# Gyro_Mode.net
KiCad netlist of a schematic drawn in Altium Designer
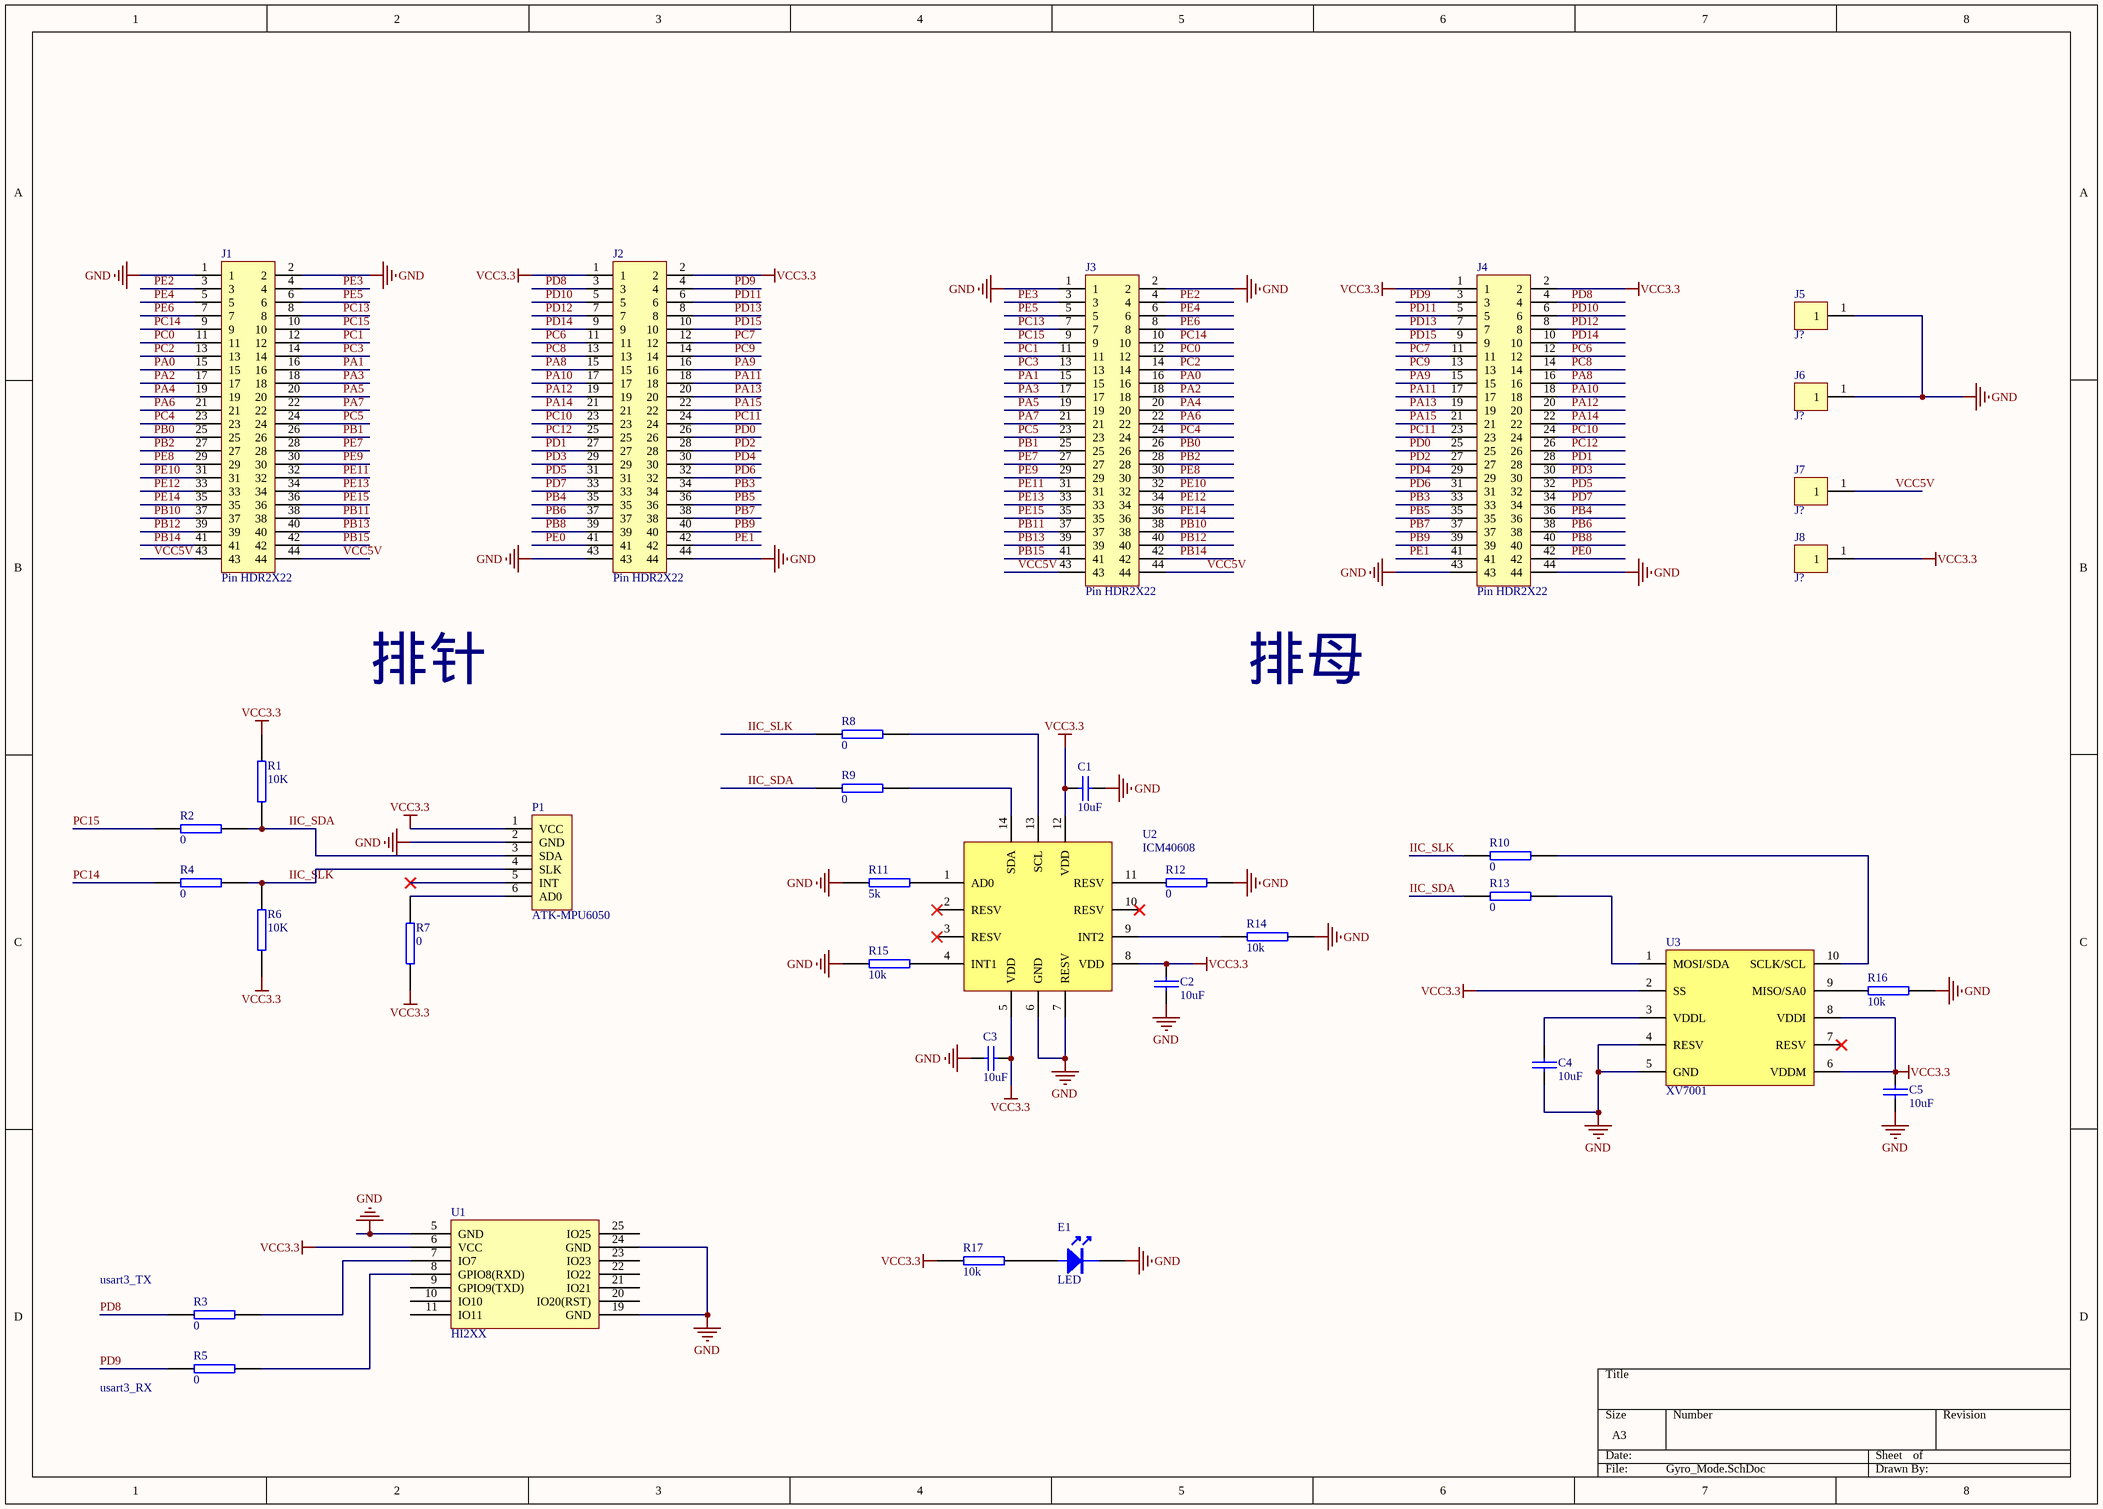
[diagram p0: Gyro_Mode.SchDoc]

(export (version "E")
  (design (tool "Eeschema 10.0.6"))
  (components
    (comp (ref "C1")
      (value "10uF")
      (footprint "0603")
      (description "无极电容")
      (libsource (lib "chenjd") (part "CAP Nonpolarity"))
    )
    (comp (ref "C2")
      (value "10uF")
      (footprint "0603")
      (description "无极电容")
      (libsource (lib "chenjd") (part "CAP Nonpolarity"))
    )
    (comp (ref "C3")
      (value "10uF")
      (footprint "0603")
      (description "无极电容")
      (libsource (lib "chenjd") (part "CAP Nonpolarity"))
    )
    (comp (ref "C4")
      (value "10uF")
      (footprint "0603")
      (description "无极电容")
      (libsource (lib "chenjd") (part "CAP Nonpolarity"))
    )
    (comp (ref "C5")
      (value "10uF")
      (footprint "0603")
      (description "无极电容")
      (libsource (lib "chenjd") (part "CAP Nonpolarity"))
    )
    (comp (ref "E1")
      (value "LED")
      (footprint "LED_0603L")
      (description "LED灯")
      (libsource (lib "chenjd") (part "LED"))
    )
    (comp (ref "J1")
      (value "Pin HDR2X22")
      (footprint "PIN HDR2X22/2.54SMD")
      (description "22pin双排2.54接口")
      (libsource (lib "chenjd") (part "Pin HDR2X22"))
    )
    (comp (ref "J2")
      (value "Pin HDR2X22")
      (footprint "PIN HDR2X22/2.54SMD")
      (description "22pin双排2.54接口")
      (libsource (lib "chenjd") (part "Pin HDR2X22"))
    )
    (comp (ref "J3")
      (value "Pin HDR2X22")
      (footprint "PIN HDR2X22/2.54SMD")
      (description "22pin双排2.54接口")
      (libsource (lib "chenjd") (part "Pin HDR2X22"))
    )
    (comp (ref "J4")
      (value "Pin HDR2X22")
      (footprint "PIN HDR2X22/2.54SMD")
      (description "22pin双排2.54接口")
      (libsource (lib "chenjd") (part "Pin HDR2X22"))
    )
    (comp (ref "J5")
      (value "J?")
      (footprint "固定柱")
      (description "固定柱")
      (libsource (lib "chenjd") (part "固定柱"))
    )
    (comp (ref "J6")
      (value "J?")
      (footprint "固定柱")
      (description "固定柱")
      (libsource (lib "chenjd") (part "固定柱"))
    )
    (comp (ref "J7")
      (value "J?")
      (footprint "固定柱")
      (description "固定柱")
      (libsource (lib "chenjd") (part "固定柱"))
    )
    (comp (ref "J8")
      (value "J?")
      (footprint "固定柱")
      (description "固定柱")
      (libsource (lib "chenjd") (part "固定柱"))
    )
    (comp (ref "P1")
      (value "ATK-MPU6050")
      (footprint "ATK-MPU6080")
      (fields (field (name "PUBLISHER") "Altium Limited"))
      (libsource (lib "chenjd") (part "ATK-MPU6050"))
    )
    (comp (ref "R1")
      (value "10K")
      (footprint "0603")
      (description "电阻")
      (libsource (lib "chenjd") (part "R"))
    )
    (comp (ref "R2") (value "0") (footprint "0603") (description "电阻") (libsource (lib "chenjd") (part "R")))
    (comp (ref "R3") (value "0") (footprint "0603") (description "电阻") (libsource (lib "chenjd") (part "R")))
    (comp (ref "R4") (value "0") (footprint "0603") (description "电阻") (libsource (lib "chenjd") (part "R")))
    (comp (ref "R5") (value "0") (footprint "0603") (description "电阻") (libsource (lib "chenjd") (part "R")))
    (comp (ref "R6")
      (value "10K")
      (footprint "0603")
      (description "电阻")
      (libsource (lib "chenjd") (part "R"))
    )
    (comp (ref "R7") (value "0") (footprint "0603") (description "电阻") (libsource (lib "chenjd") (part "R")))
    (comp (ref "R8") (value "0") (footprint "0603") (description "电阻") (libsource (lib "chenjd") (part "R")))
    (comp (ref "R9") (value "0") (footprint "0603") (description "电阻") (libsource (lib "chenjd") (part "R")))
    (comp (ref "R10") (value "0") (footprint "0603") (description "电阻") (libsource (lib "chenjd") (part "R")))
    (comp (ref "R11")
      (value "5k")
      (footprint "0603")
      (description "电阻")
      (libsource (lib "chenjd") (part "R"))
    )
    (comp (ref "R12") (value "0") (footprint "0603") (description "电阻") (libsource (lib "chenjd") (part "R")))
    (comp (ref "R13") (value "0") (footprint "0603") (description "电阻") (libsource (lib "chenjd") (part "R")))
    (comp (ref "R14")
      (value "10k")
      (footprint "0603")
      (description "电阻")
      (libsource (lib "chenjd") (part "R"))
    )
    (comp (ref "R15")
      (value "10k")
      (footprint "0603")
      (description "电阻")
      (libsource (lib "chenjd") (part "R"))
    )
    (comp (ref "R16")
      (value "10k")
      (footprint "0603")
      (description "电阻")
      (libsource (lib "chenjd") (part "R"))
    )
    (comp (ref "R17")
      (value "10k")
      (footprint "0603")
      (description "电阻")
      (libsource (lib "chenjd") (part "R"))
    )
    (comp (ref "U1")
      (value "HI2XX")
      (footprint "HI2XX_PLCC28")
      (description "HI226")
      (libsource (lib "chenjd") (part "HI2XX"))
    )
    (comp (ref "U2")
      (value "ICM40608")
      (footprint "ICM40608-LGA-14")
      (libsource (lib "chenjd") (part "ICM40608"))
    )
    (comp (ref "U3")
      (value "XV7001")
      (footprint "XV7001")
      (description "爱普生陀螺仪")
      (libsource (lib "chenjd") (part "XV7001"))
    )
  )
  (nets
    (net (code "1") (name "/IIC_SDA") (class "Default")
      (node (ref "P1") (pin "3") (pinfunction "SDA_3") (pintype "passive"))
      (node (ref "R1") (pin "1") (pinfunction "1_1") (pintype "passive"))
      (node (ref "R13") (pin "1") (pinfunction "1_1") (pintype "passive"))
      (node (ref "R2") (pin "2") (pinfunction "2_2") (pintype "passive"))
      (node (ref "R9") (pin "1") (pinfunction "1_1") (pintype "passive"))
    )
    (net (code "2") (name "/IIC_SLK") (class "Default")
      (node (ref "P1") (pin "4") (pinfunction "SLK_4") (pintype "passive"))
      (node (ref "R10") (pin "1") (pinfunction "1_1") (pintype "passive"))
      (node (ref "R4") (pin "2") (pinfunction "2_2") (pintype "passive"))
      (node (ref "R6") (pin "2") (pinfunction "2_2") (pintype "passive"))
      (node (ref "R8") (pin "1") (pinfunction "1_1") (pintype "passive"))
    )
    (net (code "3") (name "/PA0") (class "Default")
      (node (ref "J1") (pin "15") (pinfunction "15_15") (pintype "passive"))
      (node (ref "J3") (pin "16") (pinfunction "16_16") (pintype "passive"))
    )
    (net (code "4") (name "/PA1") (class "Default")
      (node (ref "J1") (pin "16") (pinfunction "16_16") (pintype "passive"))
      (node (ref "J3") (pin "15") (pinfunction "15_15") (pintype "passive"))
    )
    (net (code "5") (name "/PA2") (class "Default")
      (node (ref "J1") (pin "17") (pinfunction "17_17") (pintype "passive"))
      (node (ref "J3") (pin "18") (pinfunction "18_18") (pintype "passive"))
    )
    (net (code "6") (name "/PA3") (class "Default")
      (node (ref "J1") (pin "18") (pinfunction "18_18") (pintype "passive"))
      (node (ref "J3") (pin "17") (pinfunction "17_17") (pintype "passive"))
    )
    (net (code "7") (name "/PA4") (class "Default")
      (node (ref "J1") (pin "19") (pinfunction "19_19") (pintype "passive"))
      (node (ref "J3") (pin "20") (pinfunction "20_20") (pintype "passive"))
    )
    (net (code "8") (name "/PA5") (class "Default")
      (node (ref "J1") (pin "20") (pinfunction "20_20") (pintype "passive"))
      (node (ref "J3") (pin "19") (pinfunction "19_19") (pintype "passive"))
    )
    (net (code "9") (name "/PA6") (class "Default")
      (node (ref "J1") (pin "21") (pinfunction "21_21") (pintype "passive"))
      (node (ref "J3") (pin "22") (pinfunction "22_22") (pintype "passive"))
    )
    (net (code "10") (name "/PA7") (class "Default")
      (node (ref "J1") (pin "22") (pinfunction "22_22") (pintype "passive"))
      (node (ref "J3") (pin "21") (pinfunction "21_21") (pintype "passive"))
    )
    (net (code "11") (name "/PA8") (class "Default")
      (node (ref "J2") (pin "15") (pinfunction "15_15") (pintype "passive"))
      (node (ref "J4") (pin "16") (pinfunction "16_16") (pintype "passive"))
    )
    (net (code "12") (name "/PA9") (class "Default")
      (node (ref "J2") (pin "16") (pinfunction "16_16") (pintype "passive"))
      (node (ref "J4") (pin "15") (pinfunction "15_15") (pintype "passive"))
    )
    (net (code "13") (name "/PA10") (class "Default")
      (node (ref "J2") (pin "17") (pinfunction "17_17") (pintype "passive"))
      (node (ref "J4") (pin "18") (pinfunction "18_18") (pintype "passive"))
    )
    (net (code "14") (name "/PA11") (class "Default")
      (node (ref "J2") (pin "18") (pinfunction "18_18") (pintype "passive"))
      (node (ref "J4") (pin "17") (pinfunction "17_17") (pintype "passive"))
    )
    (net (code "15") (name "/PA12") (class "Default")
      (node (ref "J2") (pin "19") (pinfunction "19_19") (pintype "passive"))
      (node (ref "J4") (pin "20") (pinfunction "20_20") (pintype "passive"))
    )
    (net (code "16") (name "/PA13") (class "Default")
      (node (ref "J2") (pin "20") (pinfunction "20_20") (pintype "passive"))
      (node (ref "J4") (pin "19") (pinfunction "19_19") (pintype "passive"))
    )
    (net (code "17") (name "/PA14") (class "Default")
      (node (ref "J2") (pin "21") (pinfunction "21_21") (pintype "passive"))
      (node (ref "J4") (pin "22") (pinfunction "22_22") (pintype "passive"))
    )
    (net (code "18") (name "/PA15") (class "Default")
      (node (ref "J2") (pin "22") (pinfunction "22_22") (pintype "passive"))
      (node (ref "J4") (pin "21") (pinfunction "21_21") (pintype "passive"))
    )
    (net (code "19") (name "/PB0") (class "Default")
      (node (ref "J1") (pin "25") (pinfunction "25_25") (pintype "passive"))
      (node (ref "J3") (pin "26") (pinfunction "26_26") (pintype "passive"))
    )
    (net (code "20") (name "/PB1") (class "Default")
      (node (ref "J1") (pin "26") (pinfunction "26_26") (pintype "passive"))
      (node (ref "J3") (pin "25") (pinfunction "25_25") (pintype "passive"))
    )
    (net (code "21") (name "/PB2") (class "Default")
      (node (ref "J1") (pin "27") (pinfunction "27_27") (pintype "passive"))
      (node (ref "J3") (pin "28") (pinfunction "28_28") (pintype "passive"))
    )
    (net (code "22") (name "/PB3") (class "Default")
      (node (ref "J2") (pin "34") (pinfunction "34_34") (pintype "passive"))
      (node (ref "J4") (pin "33") (pinfunction "33_33") (pintype "passive"))
    )
    (net (code "23") (name "/PB4") (class "Default")
      (node (ref "J2") (pin "35") (pinfunction "35_35") (pintype "passive"))
      (node (ref "J4") (pin "36") (pinfunction "36_36") (pintype "passive"))
    )
    (net (code "24") (name "/PB5") (class "Default")
      (node (ref "J2") (pin "36") (pinfunction "36_36") (pintype "passive"))
      (node (ref "J4") (pin "35") (pinfunction "35_35") (pintype "passive"))
    )
    (net (code "25") (name "/PB6") (class "Default")
      (node (ref "J2") (pin "37") (pinfunction "37_37") (pintype "passive"))
      (node (ref "J4") (pin "38") (pinfunction "38_38") (pintype "passive"))
    )
    (net (code "26") (name "/PB7") (class "Default")
      (node (ref "J2") (pin "38") (pinfunction "38_38") (pintype "passive"))
      (node (ref "J4") (pin "37") (pinfunction "37_37") (pintype "passive"))
    )
    (net (code "27") (name "/PB8") (class "Default")
      (node (ref "J2") (pin "39") (pinfunction "39_39") (pintype "passive"))
      (node (ref "J4") (pin "40") (pinfunction "40_40") (pintype "passive"))
    )
    (net (code "28") (name "/PB9") (class "Default")
      (node (ref "J2") (pin "40") (pinfunction "40_40") (pintype "passive"))
      (node (ref "J4") (pin "39") (pinfunction "39_39") (pintype "passive"))
    )
    (net (code "29") (name "/PB10") (class "Default")
      (node (ref "J1") (pin "37") (pinfunction "37_37") (pintype "passive"))
      (node (ref "J3") (pin "38") (pinfunction "38_38") (pintype "passive"))
    )
    (net (code "30") (name "/PB11") (class "Default")
      (node (ref "J1") (pin "38") (pinfunction "38_38") (pintype "passive"))
      (node (ref "J3") (pin "37") (pinfunction "37_37") (pintype "passive"))
    )
    (net (code "31") (name "/PB12") (class "Default")
      (node (ref "J1") (pin "39") (pinfunction "39_39") (pintype "passive"))
      (node (ref "J3") (pin "40") (pinfunction "40_40") (pintype "passive"))
    )
    (net (code "32") (name "/PB13") (class "Default")
      (node (ref "J1") (pin "40") (pinfunction "40_40") (pintype "passive"))
      (node (ref "J3") (pin "39") (pinfunction "39_39") (pintype "passive"))
    )
    (net (code "33") (name "/PB14") (class "Default")
      (node (ref "J1") (pin "41") (pinfunction "41_41") (pintype "passive"))
      (node (ref "J3") (pin "42") (pinfunction "42_42") (pintype "passive"))
    )
    (net (code "34") (name "/PB15") (class "Default")
      (node (ref "J1") (pin "42") (pinfunction "42_42") (pintype "passive"))
      (node (ref "J3") (pin "41") (pinfunction "41_41") (pintype "passive"))
    )
    (net (code "35") (name "/PC0") (class "Default")
      (node (ref "J1") (pin "11") (pinfunction "11_11") (pintype "passive"))
      (node (ref "J3") (pin "12") (pinfunction "12_12") (pintype "passive"))
    )
    (net (code "36") (name "/PC1") (class "Default")
      (node (ref "J1") (pin "12") (pinfunction "12_12") (pintype "passive"))
      (node (ref "J3") (pin "11") (pinfunction "11_11") (pintype "passive"))
    )
    (net (code "37") (name "/PC2") (class "Default")
      (node (ref "J1") (pin "13") (pinfunction "13_13") (pintype "passive"))
      (node (ref "J3") (pin "14") (pinfunction "14_14") (pintype "passive"))
    )
    (net (code "38") (name "/PC3") (class "Default")
      (node (ref "J1") (pin "14") (pinfunction "14_14") (pintype "passive"))
      (node (ref "J3") (pin "13") (pinfunction "13_13") (pintype "passive"))
    )
    (net (code "39") (name "/PC4") (class "Default")
      (node (ref "J1") (pin "23") (pinfunction "23_23") (pintype "passive"))
      (node (ref "J3") (pin "24") (pinfunction "24_24") (pintype "passive"))
    )
    (net (code "40") (name "/PC5") (class "Default")
      (node (ref "J1") (pin "24") (pinfunction "24_24") (pintype "passive"))
      (node (ref "J3") (pin "23") (pinfunction "23_23") (pintype "passive"))
    )
    (net (code "41") (name "/PC6") (class "Default")
      (node (ref "J2") (pin "11") (pinfunction "11_11") (pintype "passive"))
      (node (ref "J4") (pin "12") (pinfunction "12_12") (pintype "passive"))
    )
    (net (code "42") (name "/PC7") (class "Default")
      (node (ref "J2") (pin "12") (pinfunction "12_12") (pintype "passive"))
      (node (ref "J4") (pin "11") (pinfunction "11_11") (pintype "passive"))
    )
    (net (code "43") (name "/PC8") (class "Default")
      (node (ref "J2") (pin "13") (pinfunction "13_13") (pintype "passive"))
      (node (ref "J4") (pin "14") (pinfunction "14_14") (pintype "passive"))
    )
    (net (code "44") (name "/PC9") (class "Default")
      (node (ref "J2") (pin "14") (pinfunction "14_14") (pintype "passive"))
      (node (ref "J4") (pin "13") (pinfunction "13_13") (pintype "passive"))
    )
    (net (code "45") (name "/PC10") (class "Default")
      (node (ref "J2") (pin "23") (pinfunction "23_23") (pintype "passive"))
      (node (ref "J4") (pin "24") (pinfunction "24_24") (pintype "passive"))
    )
    (net (code "46") (name "/PC11") (class "Default")
      (node (ref "J2") (pin "24") (pinfunction "24_24") (pintype "passive"))
      (node (ref "J4") (pin "23") (pinfunction "23_23") (pintype "passive"))
    )
    (net (code "47") (name "/PC12") (class "Default")
      (node (ref "J2") (pin "25") (pinfunction "25_25") (pintype "passive"))
      (node (ref "J4") (pin "26") (pinfunction "26_26") (pintype "passive"))
    )
    (net (code "48") (name "/PC13") (class "Default")
      (node (ref "J1") (pin "8") (pinfunction "8_8") (pintype "passive"))
      (node (ref "J3") (pin "7") (pinfunction "7_7") (pintype "passive"))
    )
    (net (code "49") (name "/PC14") (class "Default")
      (node (ref "J1") (pin "9") (pinfunction "9_9") (pintype "passive"))
      (node (ref "J3") (pin "10") (pinfunction "10_10") (pintype "passive"))
      (node (ref "R4") (pin "1") (pinfunction "1_1") (pintype "passive"))
    )
    (net (code "50") (name "/PC15") (class "Default")
      (node (ref "J1") (pin "10") (pinfunction "10_10") (pintype "passive"))
      (node (ref "J3") (pin "9") (pinfunction "9_9") (pintype "passive"))
      (node (ref "R2") (pin "1") (pinfunction "1_1") (pintype "passive"))
    )
    (net (code "51") (name "/PD0") (class "Default")
      (node (ref "J2") (pin "26") (pinfunction "26_26") (pintype "passive"))
      (node (ref "J4") (pin "25") (pinfunction "25_25") (pintype "passive"))
    )
    (net (code "52") (name "/PD1") (class "Default")
      (node (ref "J2") (pin "27") (pinfunction "27_27") (pintype "passive"))
      (node (ref "J4") (pin "28") (pinfunction "28_28") (pintype "passive"))
    )
    (net (code "53") (name "/PD2") (class "Default")
      (node (ref "J2") (pin "28") (pinfunction "28_28") (pintype "passive"))
      (node (ref "J4") (pin "27") (pinfunction "27_27") (pintype "passive"))
    )
    (net (code "54") (name "/PD3") (class "Default")
      (node (ref "J2") (pin "29") (pinfunction "29_29") (pintype "passive"))
      (node (ref "J4") (pin "30") (pinfunction "30_30") (pintype "passive"))
    )
    (net (code "55") (name "/PD4") (class "Default")
      (node (ref "J2") (pin "30") (pinfunction "30_30") (pintype "passive"))
      (node (ref "J4") (pin "29") (pinfunction "29_29") (pintype "passive"))
    )
    (net (code "56") (name "/PD5") (class "Default")
      (node (ref "J2") (pin "31") (pinfunction "31_31") (pintype "passive"))
      (node (ref "J4") (pin "32") (pinfunction "32_32") (pintype "passive"))
    )
    (net (code "57") (name "/PD6") (class "Default")
      (node (ref "J2") (pin "32") (pinfunction "32_32") (pintype "passive"))
      (node (ref "J4") (pin "31") (pinfunction "31_31") (pintype "passive"))
    )
    (net (code "58") (name "/PD7") (class "Default")
      (node (ref "J2") (pin "33") (pinfunction "33_33") (pintype "passive"))
      (node (ref "J4") (pin "34") (pinfunction "34_34") (pintype "passive"))
    )
    (net (code "59") (name "/PD8") (class "Default")
      (node (ref "J2") (pin "3") (pinfunction "3_3") (pintype "passive"))
      (node (ref "J4") (pin "4") (pinfunction "4_4") (pintype "passive"))
      (node (ref "R3") (pin "1") (pinfunction "1_1") (pintype "passive"))
    )
    (net (code "60") (name "/PD9") (class "Default")
      (node (ref "J2") (pin "4") (pinfunction "4_4") (pintype "passive"))
      (node (ref "J4") (pin "3") (pinfunction "3_3") (pintype "passive"))
      (node (ref "R5") (pin "1") (pinfunction "1_1") (pintype "passive"))
    )
    (net (code "61") (name "/PD10") (class "Default")
      (node (ref "J2") (pin "5") (pinfunction "5_5") (pintype "passive"))
      (node (ref "J4") (pin "6") (pinfunction "6_6") (pintype "passive"))
    )
    (net (code "62") (name "/PD11") (class "Default")
      (node (ref "J2") (pin "6") (pinfunction "6_6") (pintype "passive"))
      (node (ref "J4") (pin "5") (pinfunction "5_5") (pintype "passive"))
    )
    (net (code "63") (name "/PD12") (class "Default")
      (node (ref "J2") (pin "7") (pinfunction "7_7") (pintype "passive"))
      (node (ref "J4") (pin "8") (pinfunction "8_8") (pintype "passive"))
    )
    (net (code "64") (name "/PD13") (class "Default")
      (node (ref "J2") (pin "8") (pinfunction "8_8") (pintype "passive"))
      (node (ref "J4") (pin "7") (pinfunction "7_7") (pintype "passive"))
    )
    (net (code "65") (name "/PD14") (class "Default")
      (node (ref "J2") (pin "9") (pinfunction "9_9") (pintype "passive"))
      (node (ref "J4") (pin "10") (pinfunction "10_10") (pintype "passive"))
    )
    (net (code "66") (name "/PD15") (class "Default")
      (node (ref "J2") (pin "10") (pinfunction "10_10") (pintype "passive"))
      (node (ref "J4") (pin "9") (pinfunction "9_9") (pintype "passive"))
    )
    (net (code "67") (name "/PE0") (class "Default")
      (node (ref "J2") (pin "41") (pinfunction "41_41") (pintype "passive"))
      (node (ref "J4") (pin "42") (pinfunction "42_42") (pintype "passive"))
    )
    (net (code "68") (name "/PE1") (class "Default")
      (node (ref "J2") (pin "42") (pinfunction "42_42") (pintype "passive"))
      (node (ref "J4") (pin "41") (pinfunction "41_41") (pintype "passive"))
    )
    (net (code "69") (name "/PE2") (class "Default")
      (node (ref "J1") (pin "3") (pinfunction "3_3") (pintype "passive"))
      (node (ref "J3") (pin "4") (pinfunction "4_4") (pintype "passive"))
    )
    (net (code "70") (name "/PE3") (class "Default")
      (node (ref "J1") (pin "4") (pinfunction "4_4") (pintype "passive"))
      (node (ref "J3") (pin "3") (pinfunction "3_3") (pintype "passive"))
    )
    (net (code "71") (name "/PE4") (class "Default")
      (node (ref "J1") (pin "5") (pinfunction "5_5") (pintype "passive"))
      (node (ref "J3") (pin "6") (pinfunction "6_6") (pintype "passive"))
    )
    (net (code "72") (name "/PE5") (class "Default")
      (node (ref "J1") (pin "6") (pinfunction "6_6") (pintype "passive"))
      (node (ref "J3") (pin "5") (pinfunction "5_5") (pintype "passive"))
    )
    (net (code "73") (name "/PE6") (class "Default")
      (node (ref "J1") (pin "7") (pinfunction "7_7") (pintype "passive"))
      (node (ref "J3") (pin "8") (pinfunction "8_8") (pintype "passive"))
    )
    (net (code "74") (name "/PE7") (class "Default")
      (node (ref "J1") (pin "28") (pinfunction "28_28") (pintype "passive"))
      (node (ref "J3") (pin "27") (pinfunction "27_27") (pintype "passive"))
    )
    (net (code "75") (name "/PE8") (class "Default")
      (node (ref "J1") (pin "29") (pinfunction "29_29") (pintype "passive"))
      (node (ref "J3") (pin "30") (pinfunction "30_30") (pintype "passive"))
    )
    (net (code "76") (name "/PE9") (class "Default")
      (node (ref "J1") (pin "30") (pinfunction "30_30") (pintype "passive"))
      (node (ref "J3") (pin "29") (pinfunction "29_29") (pintype "passive"))
    )
    (net (code "77") (name "/PE10") (class "Default")
      (node (ref "J1") (pin "31") (pinfunction "31_31") (pintype "passive"))
      (node (ref "J3") (pin "32") (pinfunction "32_32") (pintype "passive"))
    )
    (net (code "78") (name "/PE11") (class "Default")
      (node (ref "J1") (pin "32") (pinfunction "32_32") (pintype "passive"))
      (node (ref "J3") (pin "31") (pinfunction "31_31") (pintype "passive"))
    )
    (net (code "79") (name "/PE12") (class "Default")
      (node (ref "J1") (pin "33") (pinfunction "33_33") (pintype "passive"))
      (node (ref "J3") (pin "34") (pinfunction "34_34") (pintype "passive"))
    )
    (net (code "80") (name "/PE13") (class "Default")
      (node (ref "J1") (pin "34") (pinfunction "34_34") (pintype "passive"))
      (node (ref "J3") (pin "33") (pinfunction "33_33") (pintype "passive"))
    )
    (net (code "81") (name "/PE14") (class "Default")
      (node (ref "J1") (pin "35") (pinfunction "35_35") (pintype "passive"))
      (node (ref "J3") (pin "36") (pinfunction "36_36") (pintype "passive"))
    )
    (net (code "82") (name "/PE15") (class "Default")
      (node (ref "J1") (pin "36") (pinfunction "36_36") (pintype "passive"))
      (node (ref "J3") (pin "35") (pinfunction "35_35") (pintype "passive"))
    )
    (net (code "83") (name "/VCC5V") (class "Default")
      (node (ref "J1") (pin "43") (pinfunction "43_43") (pintype "passive"))
      (node (ref "J1") (pin "44") (pinfunction "44_44") (pintype "passive"))
      (node (ref "J3") (pin "43") (pinfunction "43_43") (pintype "passive"))
      (node (ref "J3") (pin "44") (pinfunction "44_44") (pintype "passive"))
      (node (ref "J7") (pin "1") (pinfunction "1_1") (pintype "passive"))
    )
    (net (code "84") (name "GND") (class "Default")
      (node (ref "C1") (pin "1") (pinfunction "1_1") (pintype "passive"))
      (node (ref "C2") (pin "1") (pinfunction "1_1") (pintype "passive"))
      (node (ref "C3") (pin "1") (pinfunction "1_1") (pintype "passive"))
      (node (ref "C4") (pin "1") (pinfunction "1_1") (pintype "passive"))
      (node (ref "C5") (pin "1") (pinfunction "1_1") (pintype "passive"))
      (node (ref "E1") (pin "2") (pinfunction "2_2") (pintype "passive"))
      (node (ref "J1") (pin "1") (pinfunction "1_1") (pintype "passive"))
      (node (ref "J1") (pin "2") (pinfunction "2_2") (pintype "passive"))
      (node (ref "J2") (pin "43") (pinfunction "43_43") (pintype "passive"))
      (node (ref "J2") (pin "44") (pinfunction "44_44") (pintype "passive"))
      (node (ref "J3") (pin "1") (pinfunction "1_1") (pintype "passive"))
      (node (ref "J3") (pin "2") (pinfunction "2_2") (pintype "passive"))
      (node (ref "J4") (pin "43") (pinfunction "43_43") (pintype "passive"))
      (node (ref "J4") (pin "44") (pinfunction "44_44") (pintype "passive"))
      (node (ref "J5") (pin "1") (pinfunction "1_1") (pintype "passive"))
      (node (ref "J6") (pin "1") (pinfunction "1_1") (pintype "passive"))
      (node (ref "P1") (pin "2") (pinfunction "GND_2") (pintype "passive"))
      (node (ref "R11") (pin "1") (pinfunction "1_1") (pintype "passive"))
      (node (ref "R12") (pin "2") (pinfunction "2_2") (pintype "passive"))
      (node (ref "R14") (pin "2") (pinfunction "2_2") (pintype "passive"))
      (node (ref "R15") (pin "1") (pinfunction "1_1") (pintype "passive"))
      (node (ref "R16") (pin "2") (pinfunction "2_2") (pintype "passive"))
      (node (ref "U1") (pin "19") (pinfunction "GND_19") (pintype "passive"))
      (node (ref "U1") (pin "24") (pinfunction "GND_24") (pintype "passive"))
      (node (ref "U1") (pin "5") (pinfunction "GND_5") (pintype "passive"))
      (node (ref "U2") (pin "6") (pinfunction "GND_6") (pintype "passive"))
      (node (ref "U2") (pin "7") (pinfunction "RESV_7") (pintype "passive"))
      (node (ref "U3") (pin "4") (pinfunction "RESV_4") (pintype "passive"))
      (node (ref "U3") (pin "5") (pinfunction "GND_5") (pintype "passive"))
    )
    (net (code "85") (name "Net-(E1-Pad1)") (class "Default")
      (node (ref "E1") (pin "1") (pinfunction "1_1") (pintype "passive"))
      (node (ref "R17") (pin "2") (pinfunction "2_2") (pintype "passive"))
    )
    (net (code "86") (name "Net-(P1-AD0)") (class "Default")
      (node (ref "P1") (pin "6") (pinfunction "AD0_6") (pintype "passive"))
      (node (ref "R7") (pin "2") (pinfunction "2_2") (pintype "passive"))
    )
    (net (code "87") (name "Net-(R12-Pad1)") (class "Default")
      (node (ref "R12") (pin "1") (pinfunction "1_1") (pintype "passive"))
      (node (ref "U2") (pin "11") (pinfunction "RESV_11") (pintype "passive"))
    )
    (net (code "88") (name "Net-(U1-GPIO8(RXD))") (class "Default")
      (node (ref "R5") (pin "2") (pinfunction "2_2") (pintype "passive"))
      (node (ref "U1") (pin "8") (pinfunction "GPIO8(RXD)_8") (pintype "passive"))
    )
    (net (code "89") (name "Net-(U1-IO7)") (class "Default")
      (node (ref "R3") (pin "2") (pinfunction "2_2") (pintype "passive"))
      (node (ref "U1") (pin "7") (pinfunction "IO7_7") (pintype "passive"))
    )
    (net (code "90") (name "Net-(U2-AD0)") (class "Default")
      (node (ref "R11") (pin "2") (pinfunction "2_2") (pintype "passive"))
      (node (ref "U2") (pin "1") (pinfunction "AD0_1") (pintype "passive"))
    )
    (net (code "91") (name "Net-(U2-INT1)") (class "Default")
      (node (ref "R15") (pin "2") (pinfunction "2_2") (pintype "passive"))
      (node (ref "U2") (pin "4") (pinfunction "INT1_4") (pintype "passive"))
    )
    (net (code "92") (name "Net-(U2-INT2)") (class "Default")
      (node (ref "R14") (pin "1") (pinfunction "1_1") (pintype "passive"))
      (node (ref "U2") (pin "9") (pinfunction "INT2_9") (pintype "passive"))
    )
    (net (code "93") (name "Net-(U2-SCL)") (class "Default")
      (node (ref "R8") (pin "2") (pinfunction "2_2") (pintype "passive"))
      (node (ref "U2") (pin "13") (pinfunction "SCL_13") (pintype "passive"))
    )
    (net (code "94") (name "Net-(U2-SDA)") (class "Default")
      (node (ref "R9") (pin "2") (pinfunction "2_2") (pintype "passive"))
      (node (ref "U2") (pin "14") (pinfunction "SDA_14") (pintype "passive"))
    )
    (net (code "95") (name "Net-(U3-MISO{slash}SA0)") (class "Default")
      (node (ref "R16") (pin "1") (pinfunction "1_1") (pintype "passive"))
      (node (ref "U3") (pin "9") (pinfunction "MISO/SA0_9") (pintype "passive"))
    )
    (net (code "96") (name "Net-(U3-MOSI{slash}SDA)") (class "Default")
      (node (ref "R13") (pin "2") (pinfunction "2_2") (pintype "passive"))
      (node (ref "U3") (pin "1") (pinfunction "MOSI/SDA_1") (pintype "passive"))
    )
    (net (code "97") (name "Net-(U3-SCLK{slash}SCL)") (class "Default")
      (node (ref "R10") (pin "2") (pinfunction "2_2") (pintype "passive"))
      (node (ref "U3") (pin "10") (pinfunction "SCLK/SCL_10") (pintype "passive"))
    )
    (net (code "98") (name "Net-(U3-VDDL)") (class "Default")
      (node (ref "C4") (pin "2") (pinfunction "2_2") (pintype "passive"))
      (node (ref "U3") (pin "3") (pinfunction "VDDL_3") (pintype "passive"))
    )
    (net (code "99") (name "VCC3.3") (class "Default")
      (node (ref "C1") (pin "2") (pinfunction "2_2") (pintype "passive"))
      (node (ref "C2") (pin "2") (pinfunction "2_2") (pintype "passive"))
      (node (ref "C3") (pin "2") (pinfunction "2_2") (pintype "passive"))
      (node (ref "C5") (pin "2") (pinfunction "2_2") (pintype "passive"))
      (node (ref "J2") (pin "1") (pinfunction "1_1") (pintype "passive"))
      (node (ref "J2") (pin "2") (pinfunction "2_2") (pintype "passive"))
      (node (ref "J4") (pin "1") (pinfunction "1_1") (pintype "passive"))
      (node (ref "J4") (pin "2") (pinfunction "2_2") (pintype "passive"))
      (node (ref "J8") (pin "1") (pinfunction "1_1") (pintype "passive"))
      (node (ref "P1") (pin "1") (pinfunction "VCC_1") (pintype "passive"))
      (node (ref "R1") (pin "2") (pinfunction "2_2") (pintype "passive"))
      (node (ref "R17") (pin "1") (pinfunction "1_1") (pintype "passive"))
      (node (ref "R6") (pin "1") (pinfunction "1_1") (pintype "passive"))
      (node (ref "R7") (pin "1") (pinfunction "1_1") (pintype "passive"))
      (node (ref "U1") (pin "6") (pinfunction "VCC_6") (pintype "passive"))
      (node (ref "U2") (pin "12") (pinfunction "VDD_12") (pintype "passive"))
      (node (ref "U2") (pin "5") (pinfunction "VDD_5") (pintype "passive"))
      (node (ref "U2") (pin "8") (pinfunction "VDD_8") (pintype "passive"))
      (node (ref "U3") (pin "2") (pinfunction "SS_2") (pintype "passive"))
      (node (ref "U3") (pin "6") (pinfunction "VDDM_6") (pintype "passive"))
      (node (ref "U3") (pin "8") (pinfunction "VDDI_8") (pintype "passive"))
    )
    (net (code "100") (name "unconnected-(P1-INT-Pad5)") (class "Default")
      (node (ref "P1") (pin "5") (pinfunction "INT_5") (pintype "passive+no_connect"))
    )
    (net (code "101") (name "unconnected-(U1-GPIO9(TXD)-Pad9)") (class "Default")
      (node (ref "U1") (pin "9") (pinfunction "GPIO9(TXD)_9") (pintype "passive"))
    )
    (net (code "102") (name "unconnected-(U1-IO10-Pad10)") (class "Default")
      (node (ref "U1") (pin "10") (pinfunction "IO10_10") (pintype "passive"))
    )
    (net (code "103") (name "unconnected-(U1-IO11-Pad11)") (class "Default")
      (node (ref "U1") (pin "11") (pinfunction "IO11_11") (pintype "passive"))
    )
    (net (code "104") (name "unconnected-(U1-IO20(RST)-Pad20)") (class "Default")
      (node (ref "U1") (pin "20") (pinfunction "IO20(RST)_20") (pintype "passive"))
    )
    (net (code "105") (name "unconnected-(U1-IO21-Pad21)") (class "Default")
      (node (ref "U1") (pin "21") (pinfunction "IO21_21") (pintype "passive"))
    )
    (net (code "106") (name "unconnected-(U1-IO22-Pad22)") (class "Default")
      (node (ref "U1") (pin "22") (pinfunction "IO22_22") (pintype "passive"))
    )
    (net (code "107") (name "unconnected-(U1-IO23-Pad23)") (class "Default")
      (node (ref "U1") (pin "23") (pinfunction "IO23_23") (pintype "passive"))
    )
    (net (code "108") (name "unconnected-(U1-IO25-Pad25)") (class "Default")
      (node (ref "U1") (pin "25") (pinfunction "IO25_25") (pintype "passive"))
    )
    (net (code "109") (name "unconnected-(U2-RESV-Pad2)") (class "Default")
      (node (ref "U2") (pin "2") (pinfunction "RESV_2") (pintype "passive+no_connect"))
    )
    (net (code "110") (name "unconnected-(U2-RESV-Pad3)") (class "Default")
      (node (ref "U2") (pin "3") (pinfunction "RESV_3") (pintype "passive+no_connect"))
    )
    (net (code "111") (name "unconnected-(U2-RESV-Pad10)") (class "Default")
      (node (ref "U2") (pin "10") (pinfunction "RESV_10") (pintype "passive+no_connect"))
    )
    (net (code "112") (name "unconnected-(U3-RESV-Pad7)") (class "Default")
      (node (ref "U3") (pin "7") (pinfunction "RESV_7") (pintype "passive+no_connect"))
    )
  )
)
